# Inputs.net
KiCad netlist of a schematic drawn in Altium Designer
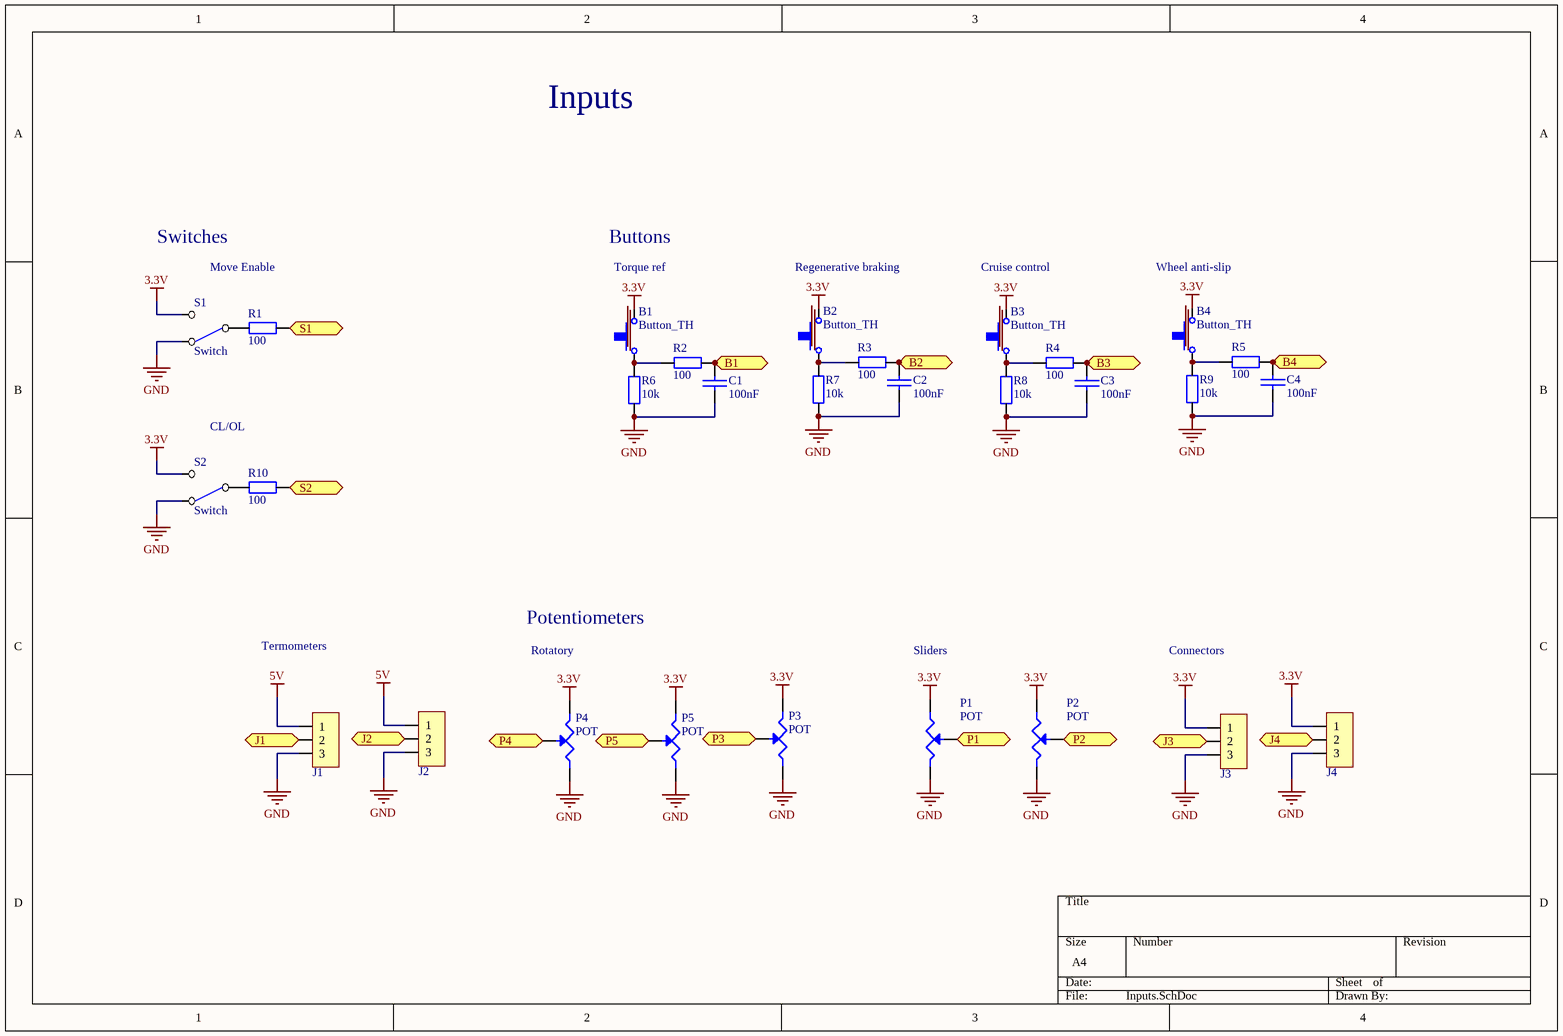
[diagram p0: Inputs.SchDoc]

(export (version "E")
  (design (tool "Eeschema 10.0.6"))
  (components
    (comp (ref "B1")
      (value "Button_TH")
      (footprint "ButtonTH")
      (libsource (lib "SCH_Lib") (part "Button_TH"))
    )
    (comp (ref "B2")
      (value "Button_TH")
      (footprint "ButtonTH")
      (libsource (lib "SCH_Lib") (part "Button_TH"))
    )
    (comp (ref "B3")
      (value "Button_TH")
      (footprint "ButtonTH")
      (libsource (lib "SCH_Lib") (part "Button_TH"))
    )
    (comp (ref "B4")
      (value "Button_TH")
      (footprint "ButtonTH")
      (libsource (lib "SCH_Lib") (part "Button_TH"))
    )
    (comp (ref "C1")
      (value "100nF")
      (footprint "1206")
      (description "Condensador")
      (libsource (lib "SCH_Lib") (part "Condensador"))
    )
    (comp (ref "C2")
      (value "100nF")
      (footprint "1206")
      (description "Condensador")
      (libsource (lib "SCH_Lib") (part "Condensador"))
    )
    (comp (ref "C3")
      (value "100nF")
      (footprint "1206")
      (description "Condensador")
      (libsource (lib "SCH_Lib") (part "Condensador"))
    )
    (comp (ref "C4")
      (value "100nF")
      (footprint "1206")
      (description "Condensador")
      (libsource (lib "SCH_Lib") (part "Condensador"))
    )
    (comp (ref "J1")
      (value "Cleva 2 vias")
      (footprint "Con3_KK_256")
      (libsource (lib "SCH_Lib") (part "Con_3"))
    )
    (comp (ref "J2")
      (value "Cleva 2 vias")
      (footprint "Con3_KK_256")
      (libsource (lib "SCH_Lib") (part "Con_3"))
    )
    (comp (ref "J3")
      (value "Cleva 2 vias")
      (footprint "Con3_KK_256")
      (libsource (lib "SCH_Lib") (part "Con_3"))
    )
    (comp (ref "J4")
      (value "Cleva 2 vias")
      (footprint "Con3_KK_256")
      (libsource (lib "SCH_Lib") (part "Con_3"))
    )
    (comp (ref "P1")
      (value "POT")
      (footprint "SliderPot_PTA6044")
      (description "POTENCIOMETRO")
      (libsource (lib "SCH_Lib") (part "POT"))
    )
    (comp (ref "P2")
      (value "POT")
      (footprint "SliderPot_PTA6044")
      (description "POTENCIOMETRO")
      (libsource (lib "SCH_Lib") (part "POT"))
    )
    (comp (ref "P3")
      (value "POT")
      (footprint "POT_RK11K1140A3L")
      (description "POTENCIOMETRO")
      (libsource (lib "SCH_Lib") (part "POT"))
    )
    (comp (ref "P4")
      (value "POT")
      (footprint "POT_RK11K1140A3L")
      (description "POTENCIOMETRO")
      (libsource (lib "SCH_Lib") (part "POT"))
    )
    (comp (ref "P5")
      (value "POT")
      (footprint "POT_RK11K1140A3L")
      (description "POTENCIOMETRO")
      (libsource (lib "SCH_Lib") (part "POT"))
    )
    (comp (ref "R1")
      (value "100")
      (footprint "1206")
      (description "Resistencia")
      (libsource (lib "SCH_Lib") (part "Resistencia"))
    )
    (comp (ref "R2")
      (value "100")
      (footprint "1206")
      (description "Resistencia")
      (libsource (lib "SCH_Lib") (part "Resistencia"))
    )
    (comp (ref "R3")
      (value "100")
      (footprint "1206")
      (description "Resistencia")
      (libsource (lib "SCH_Lib") (part "Resistencia"))
    )
    (comp (ref "R4")
      (value "100")
      (footprint "1206")
      (description "Resistencia")
      (libsource (lib "SCH_Lib") (part "Resistencia"))
    )
    (comp (ref "R5")
      (value "100")
      (footprint "1206")
      (description "Resistencia")
      (libsource (lib "SCH_Lib") (part "Resistencia"))
    )
    (comp (ref "R6")
      (value "10k")
      (footprint "1206")
      (description "Resistencia")
      (libsource (lib "SCH_Lib") (part "Resistencia"))
    )
    (comp (ref "R7")
      (value "10k")
      (footprint "1206")
      (description "Resistencia")
      (libsource (lib "SCH_Lib") (part "Resistencia"))
    )
    (comp (ref "R8")
      (value "10k")
      (footprint "1206")
      (description "Resistencia")
      (libsource (lib "SCH_Lib") (part "Resistencia"))
    )
    (comp (ref "R9")
      (value "10k")
      (footprint "1206")
      (description "Resistencia")
      (libsource (lib "SCH_Lib") (part "Resistencia"))
    )
    (comp (ref "R10")
      (value "100")
      (footprint "1206")
      (description "Resistencia")
      (libsource (lib "SCH_Lib") (part "Resistencia"))
    )
    (comp (ref "S1") (value "Switch") (footprint "SwitchTH_2Pos") (libsource (lib "SCH_Lib") (part "Switch")))
    (comp (ref "S2") (value "Switch") (footprint "SwitchTH_2Pos") (libsource (lib "SCH_Lib") (part "Switch")))
  )
  (nets
    (net (code "1") (name "/B1") (class "Default")
      (node (ref "C1") (pin "1") (pintype "passive"))
      (node (ref "R2") (pin "1") (pinfunction "1_1") (pintype "passive"))
    )
    (net (code "2") (name "/B2") (class "Default")
      (node (ref "C2") (pin "1") (pintype "passive"))
      (node (ref "R3") (pin "1") (pinfunction "1_1") (pintype "passive"))
    )
    (net (code "3") (name "/B3") (class "Default")
      (node (ref "C3") (pin "1") (pintype "passive"))
      (node (ref "R4") (pin "1") (pinfunction "1_1") (pintype "passive"))
    )
    (net (code "4") (name "/B4") (class "Default")
      (node (ref "C4") (pin "1") (pintype "passive"))
      (node (ref "R5") (pin "1") (pinfunction "1_1") (pintype "passive"))
    )
    (net (code "5") (name "/J1") (class "Default")
      (node (ref "J1") (pin "2") (pinfunction "2_2") (pintype "passive"))
    )
    (net (code "6") (name "/J2") (class "Default")
      (node (ref "J2") (pin "2") (pinfunction "2_2") (pintype "passive"))
    )
    (net (code "7") (name "/J3") (class "Default")
      (node (ref "J3") (pin "2") (pinfunction "2_2") (pintype "passive"))
    )
    (net (code "8") (name "/J4") (class "Default")
      (node (ref "J4") (pin "2") (pinfunction "2_2") (pintype "passive"))
    )
    (net (code "9") (name "/P1") (class "Default")
      (node (ref "P1") (pin "2") (pinfunction "2_2") (pintype "passive"))
    )
    (net (code "10") (name "/P2") (class "Default")
      (node (ref "P2") (pin "2") (pinfunction "2_2") (pintype "passive"))
    )
    (net (code "11") (name "/P3") (class "Default")
      (node (ref "P3") (pin "2") (pinfunction "2_2") (pintype "passive"))
    )
    (net (code "12") (name "/P4") (class "Default")
      (node (ref "P4") (pin "2") (pinfunction "2_2") (pintype "passive"))
    )
    (net (code "13") (name "/P5") (class "Default")
      (node (ref "P5") (pin "2") (pinfunction "2_2") (pintype "passive"))
    )
    (net (code "14") (name "/S1") (class "Default")
      (node (ref "R1") (pin "2") (pinfunction "2_2") (pintype "passive"))
    )
    (net (code "15") (name "/S2") (class "Default")
      (node (ref "R10") (pin "2") (pinfunction "2_2") (pintype "passive"))
    )
    (net (code "16") (name "3.3V") (class "Default")
      (node (ref "B1") (pin "0") (pinfunction "0_0") (pintype "passive"))
      (node (ref "B2") (pin "0") (pinfunction "0_0") (pintype "passive"))
      (node (ref "B3") (pin "0") (pinfunction "0_0") (pintype "passive"))
      (node (ref "B4") (pin "0") (pinfunction "0_0") (pintype "passive"))
      (node (ref "J3") (pin "1") (pinfunction "1_1") (pintype "passive"))
      (node (ref "J4") (pin "1") (pinfunction "1_1") (pintype "passive"))
      (node (ref "P1") (pin "1") (pinfunction "1_1") (pintype "passive"))
      (node (ref "P2") (pin "1") (pinfunction "1_1") (pintype "passive"))
      (node (ref "P3") (pin "3") (pinfunction "3_3") (pintype "passive"))
      (node (ref "P4") (pin "3") (pinfunction "3_3") (pintype "passive"))
      (node (ref "P5") (pin "3") (pinfunction "3_3") (pintype "passive"))
      (node (ref "S1") (pin "2") (pinfunction "ON2_2") (pintype "passive"))
      (node (ref "S2") (pin "2") (pinfunction "ON2_2") (pintype "passive"))
    )
    (net (code "17") (name "5V") (class "Default")
      (node (ref "J1") (pin "1") (pinfunction "1_1") (pintype "passive"))
      (node (ref "J2") (pin "1") (pinfunction "1_1") (pintype "passive"))
    )
    (net (code "18") (name "GND") (class "Default")
      (node (ref "C1") (pin "2") (pintype "passive"))
      (node (ref "C2") (pin "2") (pintype "passive"))
      (node (ref "C3") (pin "2") (pintype "passive"))
      (node (ref "C4") (pin "2") (pintype "passive"))
      (node (ref "J1") (pin "3") (pinfunction "3_3") (pintype "passive"))
      (node (ref "J2") (pin "3") (pinfunction "3_3") (pintype "passive"))
      (node (ref "J3") (pin "3") (pinfunction "3_3") (pintype "passive"))
      (node (ref "J4") (pin "3") (pinfunction "3_3") (pintype "passive"))
      (node (ref "P1") (pin "3") (pinfunction "3_3") (pintype "passive"))
      (node (ref "P2") (pin "3") (pinfunction "3_3") (pintype "passive"))
      (node (ref "P3") (pin "1") (pinfunction "1_1") (pintype "passive"))
      (node (ref "P4") (pin "1") (pinfunction "1_1") (pintype "passive"))
      (node (ref "P5") (pin "1") (pinfunction "1_1") (pintype "passive"))
      (node (ref "R6") (pin "2") (pinfunction "2_2") (pintype "passive"))
      (node (ref "R7") (pin "2") (pinfunction "2_2") (pintype "passive"))
      (node (ref "R8") (pin "2") (pinfunction "2_2") (pintype "passive"))
      (node (ref "R9") (pin "2") (pinfunction "2_2") (pintype "passive"))
      (node (ref "S1") (pin "0") (pinfunction "ON1_0") (pintype "passive"))
      (node (ref "S2") (pin "0") (pinfunction "ON1_0") (pintype "passive"))
    )
    (net (code "19") (name "Net-(B1-Pad1)") (class "Default")
      (node (ref "B1") (pin "1") (pinfunction "1_1") (pintype "passive"))
      (node (ref "R2") (pin "2") (pinfunction "2_2") (pintype "passive"))
      (node (ref "R6") (pin "1") (pinfunction "1_1") (pintype "passive"))
    )
    (net (code "20") (name "Net-(B2-Pad1)") (class "Default")
      (node (ref "B2") (pin "1") (pinfunction "1_1") (pintype "passive"))
      (node (ref "R3") (pin "2") (pinfunction "2_2") (pintype "passive"))
      (node (ref "R7") (pin "1") (pinfunction "1_1") (pintype "passive"))
    )
    (net (code "21") (name "Net-(B3-Pad1)") (class "Default")
      (node (ref "B3") (pin "1") (pinfunction "1_1") (pintype "passive"))
      (node (ref "R4") (pin "2") (pinfunction "2_2") (pintype "passive"))
      (node (ref "R8") (pin "1") (pinfunction "1_1") (pintype "passive"))
    )
    (net (code "22") (name "Net-(B4-Pad1)") (class "Default")
      (node (ref "B4") (pin "1") (pinfunction "1_1") (pintype "passive"))
      (node (ref "R5") (pin "2") (pinfunction "2_2") (pintype "passive"))
      (node (ref "R9") (pin "1") (pinfunction "1_1") (pintype "passive"))
    )
    (net (code "23") (name "Net-(S1-COMMON)") (class "Default")
      (node (ref "R1") (pin "1") (pinfunction "1_1") (pintype "passive"))
      (node (ref "S1") (pin "1") (pinfunction "COMMON_1") (pintype "passive"))
    )
    (net (code "24") (name "Net-(S2-COMMON)") (class "Default")
      (node (ref "R10") (pin "1") (pinfunction "1_1") (pintype "passive"))
      (node (ref "S2") (pin "1") (pinfunction "COMMON_1") (pintype "passive"))
    )
  )
)
